# PaxGeo_LEDBoard.net
KiCad netlist of a schematic drawn in EAGLE
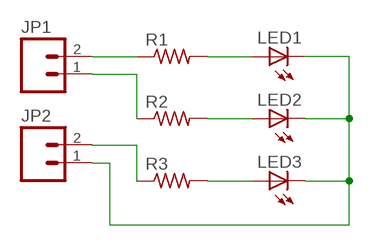
[diagram p0: schematic, sheet 1]

(export (version "E")
  (design (tool "Eeschema 10.0.6"))
  (components
    (comp (ref "JP1")
      (value "M023.5MM")
      (footprint "eagle-import:SCREWTERMINAL-3.5MM-2")
      (libsource (lib "eagle-import") (part "M023.5MM"))
    )
    (comp (ref "JP2")
      (value "M023.5MM")
      (footprint "eagle-import:SCREWTERMINAL-3.5MM-2")
      (libsource (lib "eagle-import") (part "M023.5MM"))
    )
    (comp (ref "LED1")
      (value "LED3MM")
      (footprint "eagle-import:LED3MM")
      (libsource (lib "eagle-import") (part "LED3MM"))
    )
    (comp (ref "LED2")
      (value "LED3MM")
      (footprint "eagle-import:LED3MM")
      (libsource (lib "eagle-import") (part "LED3MM"))
    )
    (comp (ref "LED3")
      (value "LED3MM")
      (footprint "eagle-import:LED3MM")
      (libsource (lib "eagle-import") (part "LED3MM"))
    )
    (comp (ref "R1")
      (value "R-US_0204/7")
      (footprint "eagle-import:0204_7")
      (libsource (lib "eagle-import") (part "R-US_0204/7"))
    )
    (comp (ref "R2")
      (value "R-US_0204/7")
      (footprint "eagle-import:0204_7")
      (libsource (lib "eagle-import") (part "R-US_0204/7"))
    )
    (comp (ref "R3")
      (value "R-US_0204/7")
      (footprint "eagle-import:0204_7")
      (libsource (lib "eagle-import") (part "R-US_0204/7"))
    )
  )
  (nets
    (net (code "1") (name "Net-(JP1-Pad1)") (class "Default")
      (node (ref "JP1") (pin "1") (pinfunction "1_1") (pintype "passive"))
      (node (ref "R2") (pin "1") (pinfunction "1_1") (pintype "passive"))
    )
    (net (code "2") (name "Net-(JP1-Pad2)") (class "Default")
      (node (ref "JP1") (pin "2") (pinfunction "2_2") (pintype "passive"))
      (node (ref "R1") (pin "1") (pinfunction "1_1") (pintype "passive"))
    )
    (net (code "3") (name "Net-(JP2-Pad2)") (class "Default")
      (node (ref "JP2") (pin "2") (pinfunction "2_2") (pintype "passive"))
      (node (ref "R3") (pin "1") (pinfunction "1_1") (pintype "passive"))
    )
    (net (code "4") (name "Net-(LED1-C)") (class "Default")
      (node (ref "JP2") (pin "1") (pinfunction "1_1") (pintype "passive"))
      (node (ref "LED1") (pin "K") (pinfunction "C_K") (pintype "passive"))
      (node (ref "LED2") (pin "K") (pinfunction "C_K") (pintype "passive"))
      (node (ref "LED3") (pin "K") (pinfunction "C_K") (pintype "passive"))
    )
    (net (code "5") (name "Net-(LED1-PadA)") (class "Default")
      (node (ref "LED1") (pin "A") (pinfunction "A_A") (pintype "passive"))
      (node (ref "R1") (pin "2") (pinfunction "2_2") (pintype "passive"))
    )
    (net (code "6") (name "Net-(LED2-PadA)") (class "Default")
      (node (ref "LED2") (pin "A") (pinfunction "A_A") (pintype "passive"))
      (node (ref "R2") (pin "2") (pinfunction "2_2") (pintype "passive"))
    )
    (net (code "7") (name "Net-(LED3-PadA)") (class "Default")
      (node (ref "LED3") (pin "A") (pinfunction "A_A") (pintype "passive"))
      (node (ref "R3") (pin "2") (pinfunction "2_2") (pintype "passive"))
    )
  )
)
